# TLC4100_SMB_charger.net
KiCad netlist of a schematic drawn in Altium Designer
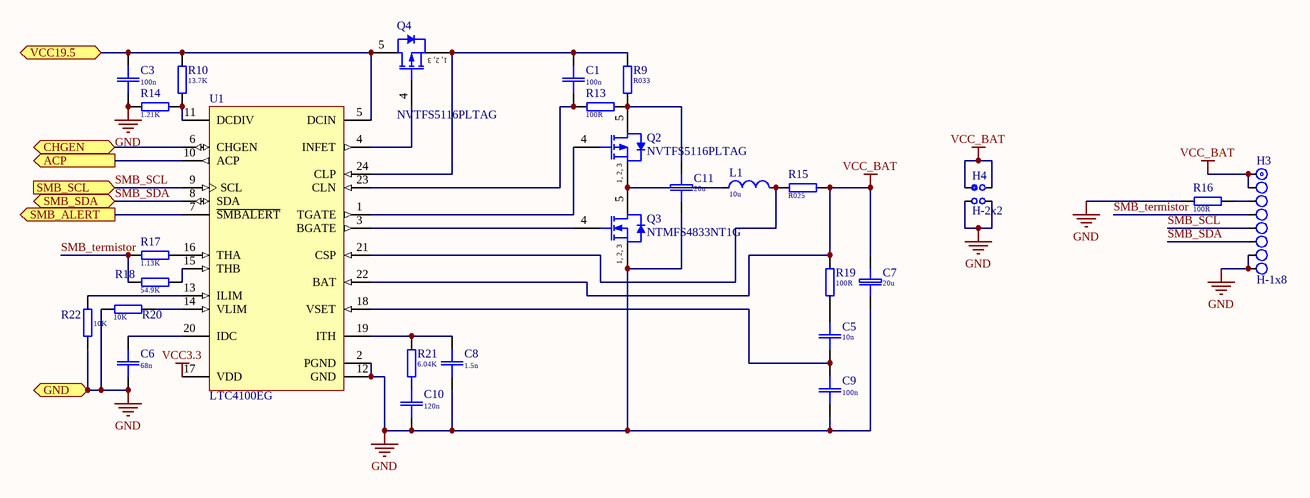
[diagram p0: TLC4100_SMB_charger.SchDoc]

(export (version "E")
  (design (tool "Eeschema 10.0.6"))
  (components
    (comp (ref "C1")
      (value "100n")
      (footprint "C0805(2013)")
      (description "SMD-0805 100V X7R 10%")
      (libsource (lib "SMD-RCL") (part "C-0805  100V 10n"))
    )
    (comp (ref "C3")
      (value "100n")
      (footprint "C0805(2013)")
      (description "SMD-0805 100V X7R 10%")
      (libsource (lib "SMD-RCL") (part "C-0805  100V 10n"))
    )
    (comp (ref "C5")
      (value "10n")
      (footprint "C0805(2013)")
      (description "SMD-0805 100V X7R 10%")
      (libsource (lib "SMD-RCL") (part "C-0805  100V 10n"))
    )
    (comp (ref "C6")
      (value "68n")
      (footprint "C0805(2013)")
      (description "SMD-0805 100V X7R 10%")
      (libsource (lib "SMD-RCL") (part "C-0805  100V 10n"))
    )
    (comp (ref "C7")
      (value "20u")
      (footprint "EL SMD Case G D10x10.3 h10.2(1010)")
      (description "EL 35V SMD Case G D10x10.3h10.5")
      (libsource (lib "SMD-RCL") (part "EL 100u/35V"))
    )
    (comp (ref "C8")
      (value "1.5n")
      (footprint "C0805(2013)")
      (description "SMD-0805 100V X7R 10%")
      (libsource (lib "SMD-RCL") (part "C-0805  100V 10n"))
    )
    (comp (ref "C9")
      (value "100n")
      (footprint "C0805(2013)")
      (description "SMD-0805 100V X7R 10%")
      (libsource (lib "SMD-RCL") (part "C-0805  100V 10n"))
    )
    (comp (ref "C10")
      (value "120n")
      (footprint "C0805(2013)")
      (description "SMD-0805 100V X7R 10%")
      (libsource (lib "SMD-RCL") (part "C-0805  100V 10n"))
    )
    (comp (ref "C11")
      (value "20u")
      (footprint "EL SMD Case G D10x10.3 h10.2(1010)")
      (description "EL 35V SMD Case G D10x10.3h10.5")
      (libsource (lib "SMD-RCL") (part "EL 100u/35V"))
    )
    (comp (ref "H3") (value "H-1x8") (footprint "J1x8") (libsource (lib "Connektor") (part "H-1x8")))
    (comp (ref "H4") (value "H-2x2") (footprint "J2x2") (libsource (lib "Connektor") (part "H-2x2")))
    (comp (ref "L1")
      (value "10u")
      (footprint "Dr-SD-73")
      (description "2.1A 0.08om 7x7x3.2mm")
      (libsource (lib "SMD-RCL") (part "L-SD-73 10uH"))
    )
    (comp (ref "Q2")
      (value "NVTFS5116PLTAG")
      (footprint "ONSC-DFN-5-488AA_V")
      (description "Power MOSFET, -60 V, -14 A, 52 mOhm, Single P-Channel, 8-Pin WDFN, Pb-Free, Tape and Reel")
      (fields (field (name "MANUFACTURER") "On Semiconductor"))
      (libsource (lib "ON Semi MOSFETs") (part "NVTFS5116PLTAG"))
    )
    (comp (ref "Q3")
      (value "NTMFS4833NT1G")
      (footprint "ONSC-DFN-5-488AA_V")
      (description "Power MOSFET, 30 V, 191 A, Single N-Channel, 5-Pin DFN, Pb-Free, Tape and Reel")
      (fields (field (name "MANUFACTURER") "On Semiconductor"))
      (libsource (lib "ON Semi MOSFETs") (part "NTMFS4833NT1G"))
    )
    (comp (ref "Q4")
      (value "NVTFS5116PLTAG")
      (footprint "ONSC-DFN-5-488AA_V")
      (description "Power MOSFET, -60 V, -14 A, 52 mOhm, Single P-Channel, 8-Pin WDFN, Pb-Free, Tape and Reel")
      (fields (field (name "MANUFACTURER") "On Semiconductor"))
      (libsource (lib "ON Semi MOSFETs") (part "NVTFS5116PLTAG"))
    )
    (comp (ref "R9")
      (value "R033")
      (footprint "R2512")
      (description "SMD 0805 0.1W 5% 150V")
      (libsource (lib "SMD-RCL") (part "R-0805"))
    )
    (comp (ref "R10")
      (value "13.7K")
      (footprint "R0805")
      (description "SMD 0805 0.1W 5% 150V")
      (libsource (lib "SMD-RCL") (part "R-0805"))
    )
    (comp (ref "R13")
      (value "100R")
      (footprint "R0805")
      (description "SMD 0805 0.1W 5% 150V")
      (libsource (lib "SMD-RCL") (part "R-0805"))
    )
    (comp (ref "R14")
      (value "1.21K")
      (footprint "R0805")
      (description "SMD 0805 0.1W 5% 150V")
      (libsource (lib "SMD-RCL") (part "R-0805"))
    )
    (comp (ref "R15")
      (value "R025")
      (footprint "R2512")
      (description "SMD 0805 0.1W 5% 150V")
      (libsource (lib "SMD-RCL") (part "R-0805"))
    )
    (comp (ref "R16")
      (value "100R")
      (footprint "R0805")
      (description "SMD 0805 0.1W 5% 150V")
      (libsource (lib "SMD-RCL") (part "R-0805"))
    )
    (comp (ref "R17")
      (value "1.13K")
      (footprint "R0805")
      (description "SMD 0805 0.1W 5% 150V")
      (libsource (lib "SMD-RCL") (part "R-0805"))
    )
    (comp (ref "R18")
      (value "54.9K")
      (footprint "R0805")
      (description "SMD 0805 0.1W 5% 150V")
      (libsource (lib "SMD-RCL") (part "R-0805"))
    )
    (comp (ref "R19")
      (value "100R")
      (footprint "R0805")
      (description "SMD 0805 0.1W 5% 150V")
      (libsource (lib "SMD-RCL") (part "R-0805"))
    )
    (comp (ref "R20")
      (value "10K")
      (footprint "R0805")
      (description "SMD 0805 0.1W 5% 150V")
      (libsource (lib "SMD-RCL") (part "R-0805"))
    )
    (comp (ref "R21")
      (value "6.04K")
      (footprint "R0805")
      (description "SMD 0805 0.1W 5% 150V")
      (libsource (lib "SMD-RCL") (part "R-0805"))
    )
    (comp (ref "R22")
      (value "10K")
      (footprint "R0805")
      (description "SMD 0805 0.1W 5% 150V")
      (libsource (lib "SMD-RCL") (part "R-0805"))
    )
    (comp (ref "U1")
      (value "LTC4100EG")
      (footprint "LT-G-24_N")
      (description "Smart Battery Charger Controller, 6 to 28 V Vin, 24-pin SOP (G-24), -40 to 85 degC")
      (fields (field (name "MANUFACTURER") "Linear Technology"))
      (libsource (lib "Linear Technology Power Management Battery Management") (part "LTC4100EG"))
    )
  )
  (nets
    (net (code "1") (name "/ACP") (class "Default")
      (node (ref "U1") (pin "10") (pinfunction "ACP_10") (pintype "output"))
    )
    (net (code "2") (name "/CHGEN") (class "Default")
      (node (ref "U1") (pin "6") (pinfunction "CHGEN_6") (pintype "bidirectional"))
    )
    (net (code "3") (name "/SMB_ALERT") (class "Default")
      (node (ref "U1") (pin "7") (pinfunction "~{SMBALERT}_7") (pintype "open_collector"))
    )
    (net (code "4") (name "/SMB_SCL") (class "Default")
      (node (ref "H3") (pin "5") (pinfunction "5_5") (pintype "passive"))
      (node (ref "U1") (pin "9") (pinfunction "SCL_9") (pintype "input"))
    )
    (net (code "5") (name "/SMB_SDA") (class "Default")
      (node (ref "H3") (pin "6") (pinfunction "6_6") (pintype "passive"))
      (node (ref "U1") (pin "8") (pinfunction "SDA_8") (pintype "bidirectional"))
    )
    (net (code "6") (name "/SMB_termistor") (class "Default")
      (node (ref "H3") (pin "4") (pinfunction "4_4") (pintype "passive"))
      (node (ref "R17") (pin "2") (pinfunction "2_2") (pintype "passive"))
      (node (ref "R18") (pin "2") (pinfunction "2_2") (pintype "passive"))
    )
    (net (code "7") (name "/VCC19.5") (class "Default")
      (node (ref "C3") (pin "1") (pinfunction "1_1") (pintype "passive"))
      (node (ref "Q4") (pin "5") (pinfunction "D_5") (pintype "passive"))
      (node (ref "R10") (pin "1") (pinfunction "1_1") (pintype "passive"))
      (node (ref "U1") (pin "5") (pinfunction "DCIN_5") (pintype "power_in"))
    )
    (net (code "8") (name "GND") (class "Default")
      (node (ref "C10") (pin "2") (pinfunction "2_2") (pintype "passive"))
      (node (ref "C11") (pin "2") (pinfunction "-_2") (pintype "passive"))
      (node (ref "C3") (pin "2") (pinfunction "2_2") (pintype "passive"))
      (node (ref "C6") (pin "2") (pinfunction "2_2") (pintype "passive"))
      (node (ref "C7") (pin "2") (pinfunction "-_2") (pintype "passive"))
      (node (ref "C8") (pin "2") (pinfunction "2_2") (pintype "passive"))
      (node (ref "C9") (pin "2") (pinfunction "2_2") (pintype "passive"))
      (node (ref "H3") (pin "7") (pinfunction "7_7") (pintype "passive"))
      (node (ref "H3") (pin "8") (pinfunction "8_8") (pintype "passive"))
      (node (ref "H4") (pin "3") (pinfunction "3_3") (pintype "passive"))
      (node (ref "H4") (pin "4") (pinfunction "4_4") (pintype "passive"))
      (node (ref "Q3") (pin "1") (pinfunction "S_1") (pintype "passive"))
      (node (ref "Q3") (pin "2") (pinfunction "S_2") (pintype "passive"))
      (node (ref "Q3") (pin "3") (pinfunction "S_3") (pintype "passive"))
      (node (ref "R14") (pin "2") (pinfunction "2_2") (pintype "passive"))
      (node (ref "R16") (pin "1") (pinfunction "1_1") (pintype "passive"))
      (node (ref "R20") (pin "1") (pinfunction "1_1") (pintype "passive"))
      (node (ref "R22") (pin "1") (pinfunction "1_1") (pintype "passive"))
      (node (ref "U1") (pin "12") (pinfunction "GND_12") (pintype "power_in"))
      (node (ref "U1") (pin "2") (pinfunction "PGND_2") (pintype "power_in"))
    )
    (net (code "9") (name "Net-(C5-Pad1)") (class "Default")
      (node (ref "C5") (pin "1") (pinfunction "1_1") (pintype "passive"))
      (node (ref "R19") (pin "2") (pinfunction "2_2") (pintype "passive"))
    )
    (net (code "10") (name "Net-(C10-Pad1)") (class "Default")
      (node (ref "C10") (pin "1") (pinfunction "1_1") (pintype "passive"))
      (node (ref "R21") (pin "2") (pinfunction "2_2") (pintype "passive"))
    )
    (net (code "11") (name "Net-(C11-+)") (class "Default")
      (node (ref "C11") (pin "1") (pinfunction "+_1") (pintype "passive"))
      (node (ref "Q2") (pin "5") (pinfunction "D_5") (pintype "passive"))
      (node (ref "R13") (pin "1") (pinfunction "1_1") (pintype "passive"))
      (node (ref "R9") (pin "1") (pinfunction "1_1") (pintype "passive"))
    )
    (net (code "12") (name "Net-(H3-Pad3)") (class "Default")
      (node (ref "H3") (pin "3") (pinfunction "3_3") (pintype "passive"))
      (node (ref "R16") (pin "2") (pinfunction "2_2") (pintype "passive"))
    )
    (net (code "13") (name "Net-(Q2-G)") (class "Default")
      (node (ref "Q2") (pin "4") (pinfunction "G_4") (pintype "passive"))
      (node (ref "U1") (pin "1") (pinfunction "TGATE_1") (pintype "output"))
    )
    (net (code "14") (name "Net-(Q3-D)") (class "Default")
      (node (ref "L1") (pin "1") (pinfunction "1_1") (pintype "passive"))
      (node (ref "Q2") (pin "1") (pinfunction "S_1") (pintype "passive"))
      (node (ref "Q2") (pin "2") (pinfunction "S_2") (pintype "passive"))
      (node (ref "Q2") (pin "3") (pinfunction "S_3") (pintype "passive"))
      (node (ref "Q3") (pin "5") (pinfunction "D_5") (pintype "passive"))
    )
    (net (code "15") (name "Net-(Q3-G)") (class "Default")
      (node (ref "Q3") (pin "4") (pinfunction "G_4") (pintype "passive"))
      (node (ref "U1") (pin "3") (pinfunction "BGATE_3") (pintype "output"))
    )
    (net (code "16") (name "Net-(Q4-G)") (class "Default")
      (node (ref "Q4") (pin "4") (pinfunction "G_4") (pintype "passive"))
      (node (ref "U1") (pin "4") (pinfunction "INFET_4") (pintype "output"))
    )
    (net (code "17") (name "Net-(U1-CLN)") (class "Default")
      (node (ref "C1") (pin "2") (pinfunction "2_2") (pintype "passive"))
      (node (ref "R13") (pin "2") (pinfunction "2_2") (pintype "passive"))
      (node (ref "U1") (pin "23") (pinfunction "CLN_23") (pintype "input"))
    )
    (net (code "18") (name "Net-(U1-CLP)") (class "Default")
      (node (ref "C1") (pin "1") (pinfunction "1_1") (pintype "passive"))
      (node (ref "Q4") (pin "1") (pinfunction "S_1") (pintype "passive"))
      (node (ref "Q4") (pin "2") (pinfunction "S_2") (pintype "passive"))
      (node (ref "Q4") (pin "3") (pinfunction "S_3") (pintype "passive"))
      (node (ref "R9") (pin "2") (pinfunction "2_2") (pintype "passive"))
      (node (ref "U1") (pin "24") (pinfunction "CLP_24") (pintype "input"))
    )
    (net (code "19") (name "Net-(U1-CSP)") (class "Default")
      (node (ref "L1") (pin "2") (pinfunction "2_2") (pintype "passive"))
      (node (ref "R15") (pin "2") (pinfunction "2_2") (pintype "passive"))
      (node (ref "U1") (pin "21") (pinfunction "CSP_21") (pintype "input"))
    )
    (net (code "20") (name "Net-(U1-DCDIV)") (class "Default")
      (node (ref "R10") (pin "2") (pinfunction "2_2") (pintype "passive"))
      (node (ref "R14") (pin "1") (pinfunction "1_1") (pintype "passive"))
      (node (ref "U1") (pin "11") (pinfunction "DCDIV_11") (pintype "power_in"))
    )
    (net (code "21") (name "Net-(U1-IDC)") (class "Default")
      (node (ref "C6") (pin "1") (pinfunction "1_1") (pintype "passive"))
      (node (ref "U1") (pin "20") (pinfunction "IDC_20") (pintype "passive"))
    )
    (net (code "22") (name "Net-(U1-ILIM)") (class "Default")
      (node (ref "R22") (pin "2") (pinfunction "2_2") (pintype "passive"))
      (node (ref "U1") (pin "13") (pinfunction "ILIM_13") (pintype "input"))
    )
    (net (code "23") (name "Net-(U1-ITH)") (class "Default")
      (node (ref "C8") (pin "1") (pinfunction "1_1") (pintype "passive"))
      (node (ref "R21") (pin "1") (pinfunction "1_1") (pintype "passive"))
      (node (ref "U1") (pin "19") (pinfunction "ITH_19") (pintype "passive"))
    )
    (net (code "24") (name "Net-(U1-THA)") (class "Default")
      (node (ref "R17") (pin "1") (pinfunction "1_1") (pintype "passive"))
      (node (ref "U1") (pin "16") (pinfunction "THA_16") (pintype "input"))
    )
    (net (code "25") (name "Net-(U1-THB)") (class "Default")
      (node (ref "R18") (pin "1") (pinfunction "1_1") (pintype "passive"))
      (node (ref "U1") (pin "15") (pinfunction "THB_15") (pintype "input"))
    )
    (net (code "26") (name "Net-(U1-VLIM)") (class "Default")
      (node (ref "R20") (pin "2") (pinfunction "2_2") (pintype "passive"))
      (node (ref "U1") (pin "14") (pinfunction "VLIM_14") (pintype "input"))
    )
    (net (code "27") (name "Net-(U1-VSET)") (class "Default")
      (node (ref "C5") (pin "2") (pinfunction "2_2") (pintype "passive"))
      (node (ref "C9") (pin "1") (pinfunction "1_1") (pintype "passive"))
      (node (ref "U1") (pin "18") (pinfunction "VSET_18") (pintype "input"))
    )
    (net (code "28") (name "VCC3.3") (class "Default")
      (node (ref "U1") (pin "17") (pinfunction "VDD_17") (pintype "power_in"))
    )
    (net (code "29") (name "VCC_BAT") (class "Default")
      (node (ref "C7") (pin "1") (pinfunction "+_1") (pintype "passive"))
      (node (ref "H3") (pin "1") (pinfunction "1_1") (pintype "passive"))
      (node (ref "H3") (pin "2") (pinfunction "2_2") (pintype "passive"))
      (node (ref "H4") (pin "1") (pinfunction "1_1") (pintype "passive"))
      (node (ref "H4") (pin "2") (pinfunction "2_2") (pintype "passive"))
      (node (ref "R15") (pin "1") (pinfunction "1_1") (pintype "passive"))
      (node (ref "R19") (pin "1") (pinfunction "1_1") (pintype "passive"))
      (node (ref "U1") (pin "22") (pinfunction "BAT_22") (pintype "input"))
    )
  )
)
